# I2C_MUX.net
KiCad netlist of a schematic drawn in EAGLE
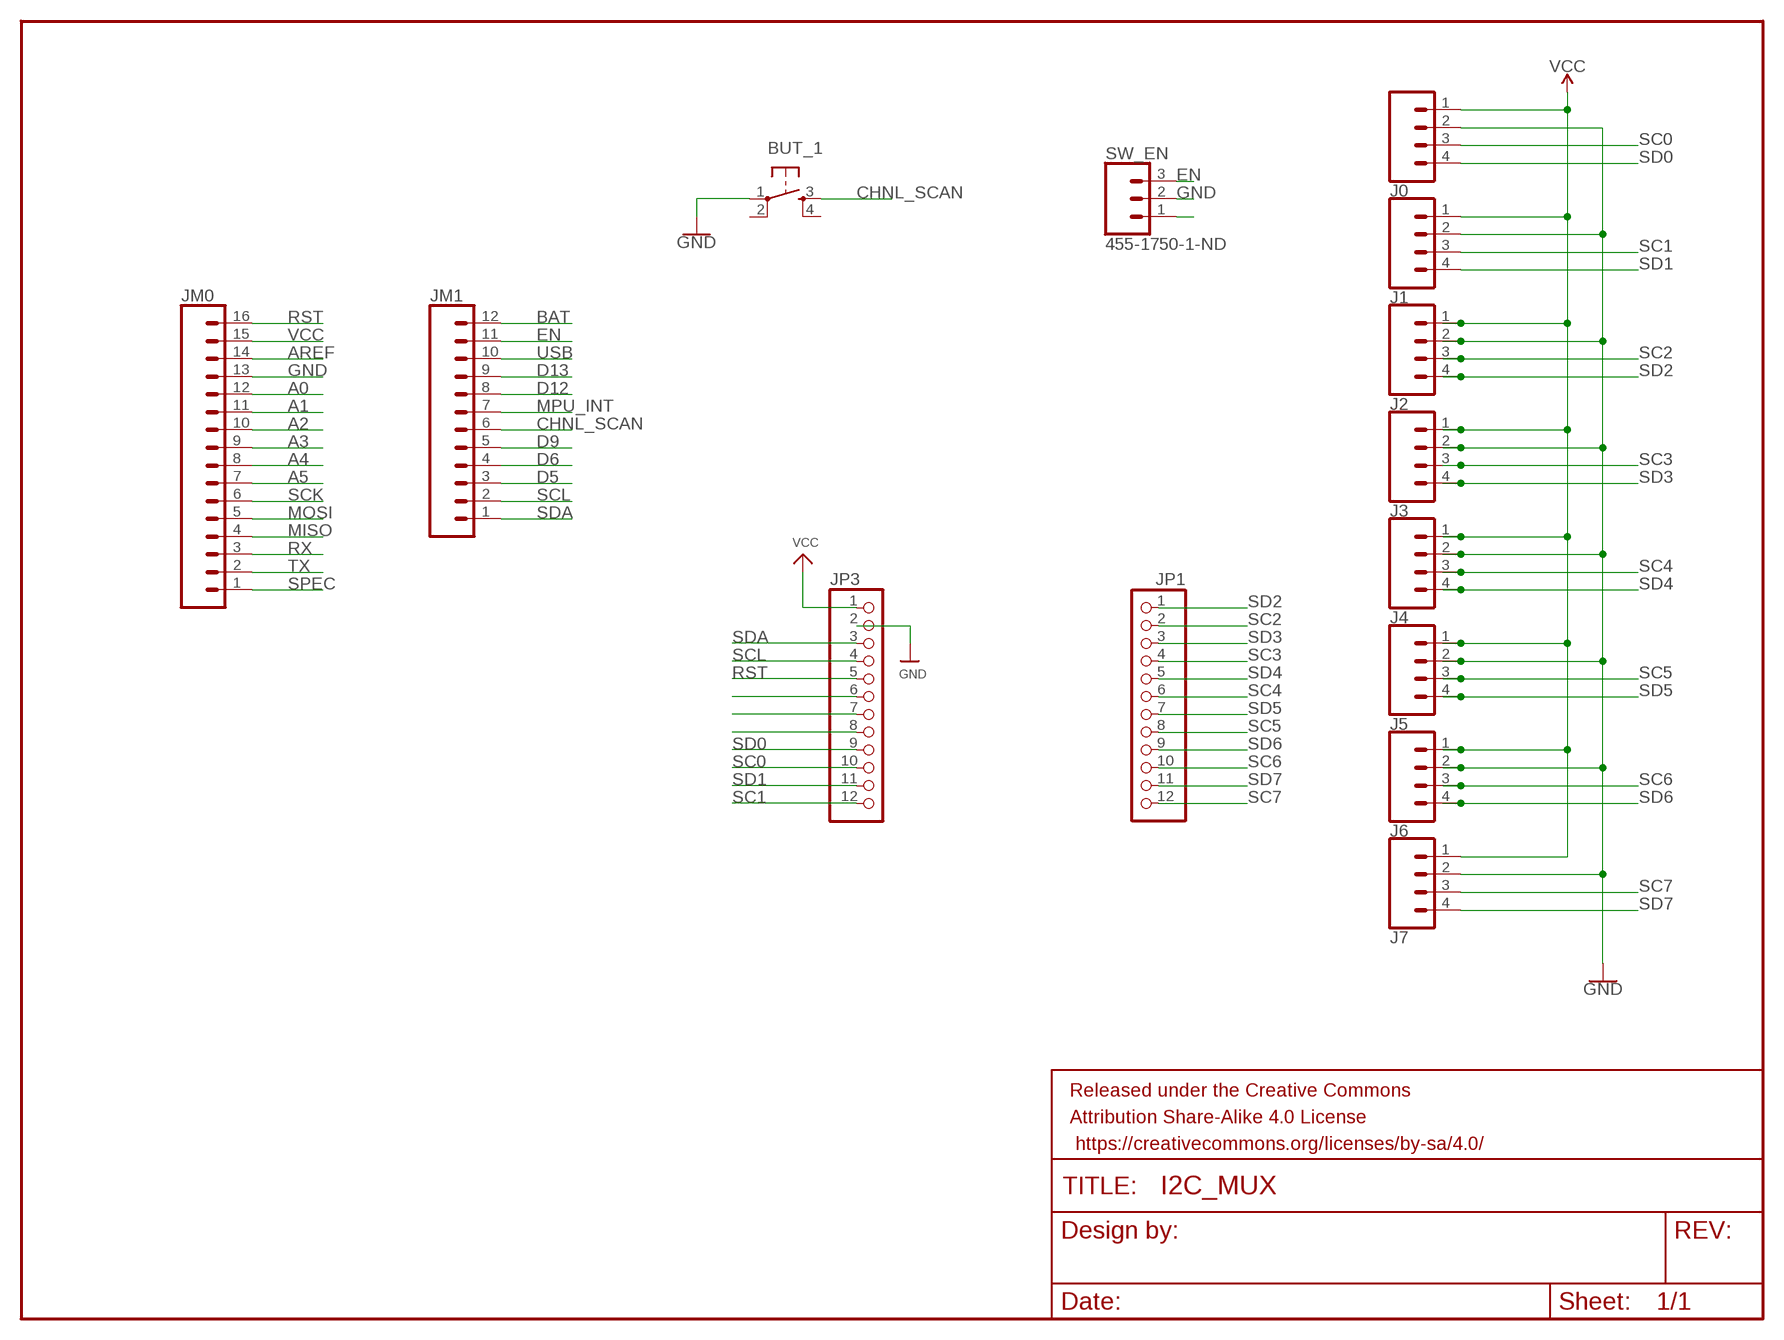
[diagram p0: schematic, sheet 1]

(export (version "E")
  (design (tool "Eeschema 10.0.6"))
  (components
    (comp (ref "BUT_1")
      (value "TAC_SWITCHPTH")
      (footprint "eagle-import:TACTILE-PTH")
      (libsource (lib "eagle-import") (part "TAC_SWITCHPTH"))
    )
    (comp (ref "FRAME1")
      (value "FRAME-LETTER")
      (footprint "eagle-import:CREATIVE_COMMONS")
      (libsource (lib "eagle-import") (part "FRAME-LETTER"))
    )
    (comp (ref "J0")
      (value "CONN_04POLAR")
      (footprint "eagle-import:MOLEX-1X4")
      (libsource (lib "eagle-import") (part "CONN_04POLAR"))
    )
    (comp (ref "J1")
      (value "CONN_04POLAR")
      (footprint "eagle-import:MOLEX-1X4")
      (libsource (lib "eagle-import") (part "CONN_04POLAR"))
    )
    (comp (ref "J2")
      (value "CONN_04POLAR")
      (footprint "eagle-import:MOLEX-1X4")
      (libsource (lib "eagle-import") (part "CONN_04POLAR"))
    )
    (comp (ref "J3")
      (value "CONN_04POLAR")
      (footprint "eagle-import:MOLEX-1X4")
      (libsource (lib "eagle-import") (part "CONN_04POLAR"))
    )
    (comp (ref "J4")
      (value "CONN_04POLAR")
      (footprint "eagle-import:MOLEX-1X4")
      (libsource (lib "eagle-import") (part "CONN_04POLAR"))
    )
    (comp (ref "J5")
      (value "CONN_04POLAR")
      (footprint "eagle-import:MOLEX-1X4")
      (libsource (lib "eagle-import") (part "CONN_04POLAR"))
    )
    (comp (ref "J6")
      (value "CONN_04POLAR")
      (footprint "eagle-import:MOLEX-1X4")
      (libsource (lib "eagle-import") (part "CONN_04POLAR"))
    )
    (comp (ref "J7")
      (value "CONN_04POLAR")
      (footprint "eagle-import:MOLEX-1X4")
      (libsource (lib "eagle-import") (part "CONN_04POLAR"))
    )
    (comp (ref "JM0")
      (value "CONN_16")
      (footprint "eagle-import:1X16")
      (libsource (lib "eagle-import") (part "CONN_16"))
    )
    (comp (ref "JM1")
      (value "CONN_12")
      (footprint "eagle-import:1X12")
      (libsource (lib "eagle-import") (part "CONN_12"))
    )
    (comp (ref "JP1")
      (value "HEADER-1X12")
      (footprint "eagle-import:1X12_ROUND")
      (libsource (lib "eagle-import") (part "HEADER-1X12"))
    )
    (comp (ref "JP3")
      (value "HEADER-1X12")
      (footprint "eagle-import:1X12_ROUND")
      (libsource (lib "eagle-import") (part "HEADER-1X12"))
    )
    (comp (ref "SW_EN")
      (value "455-1750-1-ND")
      (footprint "eagle-import:1X03")
      (libsource (lib "eagle-import") (part "CONN_03"))
    )
  )
  (nets
    (net (code "1") (name "/A0") (class "Default")
      (node (ref "JM0") (pin "12") (pinfunction "12_12") (pintype "passive"))
    )
    (net (code "2") (name "/A1") (class "Default")
      (node (ref "JM0") (pin "11") (pinfunction "11_11") (pintype "passive"))
    )
    (net (code "3") (name "/A2") (class "Default")
      (node (ref "JM0") (pin "10") (pinfunction "10_10") (pintype "passive"))
    )
    (net (code "4") (name "/A3") (class "Default")
      (node (ref "JM0") (pin "9") (pinfunction "9_9") (pintype "passive"))
    )
    (net (code "5") (name "/A4") (class "Default")
      (node (ref "JM0") (pin "8") (pinfunction "8_8") (pintype "passive"))
    )
    (net (code "6") (name "/A5") (class "Default")
      (node (ref "JM0") (pin "7") (pinfunction "7_7") (pintype "passive"))
    )
    (net (code "7") (name "/AREF") (class "Default")
      (node (ref "JM0") (pin "14") (pinfunction "14_14") (pintype "passive"))
    )
    (net (code "8") (name "/BAT") (class "Default")
      (node (ref "JM1") (pin "12") (pinfunction "12_12") (pintype "passive"))
    )
    (net (code "9") (name "/CHNL_SCAN") (class "Default")
      (node (ref "BUT_1") (pin "3") (pinfunction "3_3") (pintype "passive"))
      (node (ref "JM1") (pin "6") (pinfunction "6_6") (pintype "passive"))
    )
    (net (code "10") (name "/D5") (class "Default")
      (node (ref "JM1") (pin "3") (pinfunction "3_3") (pintype "passive"))
    )
    (net (code "11") (name "/D6") (class "Default")
      (node (ref "JM1") (pin "4") (pinfunction "4_4") (pintype "passive"))
    )
    (net (code "12") (name "/D9") (class "Default")
      (node (ref "JM1") (pin "5") (pinfunction "5_5") (pintype "passive"))
    )
    (net (code "13") (name "/D12") (class "Default")
      (node (ref "JM1") (pin "8") (pinfunction "8_8") (pintype "passive"))
    )
    (net (code "14") (name "/D13") (class "Default")
      (node (ref "JM1") (pin "9") (pinfunction "9_9") (pintype "passive"))
    )
    (net (code "15") (name "/EN") (class "Default")
      (node (ref "JM1") (pin "11") (pinfunction "11_11") (pintype "passive"))
      (node (ref "SW_EN") (pin "3") (pinfunction "3_3") (pintype "passive"))
    )
    (net (code "16") (name "/MISO") (class "Default")
      (node (ref "JM0") (pin "4") (pinfunction "4_4") (pintype "passive"))
    )
    (net (code "17") (name "/MOSI") (class "Default")
      (node (ref "JM0") (pin "5") (pinfunction "5_5") (pintype "passive"))
    )
    (net (code "18") (name "/MPU_INT") (class "Default")
      (node (ref "JM1") (pin "7") (pinfunction "7_7") (pintype "passive"))
    )
    (net (code "19") (name "/RST") (class "Default")
      (node (ref "JM0") (pin "16") (pinfunction "16_16") (pintype "passive"))
      (node (ref "JP3") (pin "5") (pinfunction "5_5") (pintype "passive"))
    )
    (net (code "20") (name "/RX") (class "Default")
      (node (ref "JM0") (pin "3") (pinfunction "3_3") (pintype "passive"))
    )
    (net (code "21") (name "/SC0") (class "Default")
      (node (ref "J0") (pin "3") (pinfunction "3_3") (pintype "passive"))
      (node (ref "JP3") (pin "10") (pinfunction "10_10") (pintype "passive"))
    )
    (net (code "22") (name "/SC1") (class "Default")
      (node (ref "J1") (pin "3") (pinfunction "3_3") (pintype "passive"))
      (node (ref "JP3") (pin "12") (pinfunction "12_12") (pintype "passive"))
    )
    (net (code "23") (name "/SC2") (class "Default")
      (node (ref "J2") (pin "3") (pinfunction "3_3") (pintype "passive"))
      (node (ref "JP1") (pin "2") (pinfunction "2_2") (pintype "passive"))
    )
    (net (code "24") (name "/SC3") (class "Default")
      (node (ref "J3") (pin "3") (pinfunction "3_3") (pintype "passive"))
      (node (ref "JP1") (pin "4") (pinfunction "4_4") (pintype "passive"))
    )
    (net (code "25") (name "/SC4") (class "Default")
      (node (ref "J4") (pin "3") (pinfunction "3_3") (pintype "passive"))
      (node (ref "JP1") (pin "6") (pinfunction "6_6") (pintype "passive"))
    )
    (net (code "26") (name "/SC5") (class "Default")
      (node (ref "J5") (pin "3") (pinfunction "3_3") (pintype "passive"))
      (node (ref "JP1") (pin "8") (pinfunction "8_8") (pintype "passive"))
    )
    (net (code "27") (name "/SC6") (class "Default")
      (node (ref "J6") (pin "3") (pinfunction "3_3") (pintype "passive"))
      (node (ref "JP1") (pin "10") (pinfunction "10_10") (pintype "passive"))
    )
    (net (code "28") (name "/SC7") (class "Default")
      (node (ref "J7") (pin "3") (pinfunction "3_3") (pintype "passive"))
      (node (ref "JP1") (pin "12") (pinfunction "12_12") (pintype "passive"))
    )
    (net (code "29") (name "/SCK") (class "Default")
      (node (ref "JM0") (pin "6") (pinfunction "6_6") (pintype "passive"))
    )
    (net (code "30") (name "/SCL") (class "Default")
      (node (ref "JM1") (pin "2") (pinfunction "2_2") (pintype "passive"))
      (node (ref "JP3") (pin "4") (pinfunction "4_4") (pintype "passive"))
    )
    (net (code "31") (name "/SD0") (class "Default")
      (node (ref "J0") (pin "4") (pinfunction "4_4") (pintype "passive"))
      (node (ref "JP3") (pin "9") (pinfunction "9_9") (pintype "passive"))
    )
    (net (code "32") (name "/SD1") (class "Default")
      (node (ref "J1") (pin "4") (pinfunction "4_4") (pintype "passive"))
      (node (ref "JP3") (pin "11") (pinfunction "11_11") (pintype "passive"))
    )
    (net (code "33") (name "/SD2") (class "Default")
      (node (ref "J2") (pin "4") (pinfunction "4_4") (pintype "passive"))
      (node (ref "JP1") (pin "1") (pinfunction "1_1") (pintype "passive"))
    )
    (net (code "34") (name "/SD3") (class "Default")
      (node (ref "J3") (pin "4") (pinfunction "4_4") (pintype "passive"))
      (node (ref "JP1") (pin "3") (pinfunction "3_3") (pintype "passive"))
    )
    (net (code "35") (name "/SD4") (class "Default")
      (node (ref "J4") (pin "4") (pinfunction "4_4") (pintype "passive"))
      (node (ref "JP1") (pin "5") (pinfunction "5_5") (pintype "passive"))
    )
    (net (code "36") (name "/SD5") (class "Default")
      (node (ref "J5") (pin "4") (pinfunction "4_4") (pintype "passive"))
      (node (ref "JP1") (pin "7") (pinfunction "7_7") (pintype "passive"))
    )
    (net (code "37") (name "/SD6") (class "Default")
      (node (ref "J6") (pin "4") (pinfunction "4_4") (pintype "passive"))
      (node (ref "JP1") (pin "9") (pinfunction "9_9") (pintype "passive"))
    )
    (net (code "38") (name "/SD7") (class "Default")
      (node (ref "J7") (pin "4") (pinfunction "4_4") (pintype "passive"))
      (node (ref "JP1") (pin "11") (pinfunction "11_11") (pintype "passive"))
    )
    (net (code "39") (name "/SDA") (class "Default")
      (node (ref "JM1") (pin "1") (pinfunction "1_1") (pintype "passive"))
      (node (ref "JP3") (pin "3") (pinfunction "3_3") (pintype "passive"))
    )
    (net (code "40") (name "/SPEC") (class "Default")
      (node (ref "JM0") (pin "1") (pinfunction "1_1") (pintype "passive"))
    )
    (net (code "41") (name "/TX") (class "Default")
      (node (ref "JM0") (pin "2") (pinfunction "2_2") (pintype "passive"))
    )
    (net (code "42") (name "/USB") (class "Default")
      (node (ref "JM1") (pin "10") (pinfunction "10_10") (pintype "passive"))
    )
    (net (code "43") (name "GND") (class "Default")
      (node (ref "BUT_1") (pin "1") (pinfunction "1_1") (pintype "passive"))
      (node (ref "J0") (pin "2") (pinfunction "2_2") (pintype "passive"))
      (node (ref "J1") (pin "2") (pinfunction "2_2") (pintype "passive"))
      (node (ref "J2") (pin "2") (pinfunction "2_2") (pintype "passive"))
      (node (ref "J3") (pin "2") (pinfunction "2_2") (pintype "passive"))
      (node (ref "J4") (pin "2") (pinfunction "2_2") (pintype "passive"))
      (node (ref "J5") (pin "2") (pinfunction "2_2") (pintype "passive"))
      (node (ref "J6") (pin "2") (pinfunction "2_2") (pintype "passive"))
      (node (ref "J7") (pin "2") (pinfunction "2_2") (pintype "passive"))
      (node (ref "JM0") (pin "13") (pinfunction "13_13") (pintype "passive"))
      (node (ref "JP3") (pin "2") (pinfunction "2_2") (pintype "passive"))
      (node (ref "SW_EN") (pin "2") (pinfunction "2_2") (pintype "passive"))
    )
    (net (code "44") (name "VCC") (class "Default")
      (node (ref "J0") (pin "1") (pinfunction "1_1") (pintype "passive"))
      (node (ref "J1") (pin "1") (pinfunction "1_1") (pintype "passive"))
      (node (ref "J2") (pin "1") (pinfunction "1_1") (pintype "passive"))
      (node (ref "J3") (pin "1") (pinfunction "1_1") (pintype "passive"))
      (node (ref "J4") (pin "1") (pinfunction "1_1") (pintype "passive"))
      (node (ref "J5") (pin "1") (pinfunction "1_1") (pintype "passive"))
      (node (ref "J6") (pin "1") (pinfunction "1_1") (pintype "passive"))
      (node (ref "J7") (pin "1") (pinfunction "1_1") (pintype "passive"))
      (node (ref "JM0") (pin "15") (pinfunction "15_15") (pintype "passive"))
      (node (ref "JP3") (pin "1") (pinfunction "1_1") (pintype "passive"))
    )
    (net (code "45") (name "unconnected-(BUT_1-Pad2)") (class "Default")
      (node (ref "BUT_1") (pin "2") (pinfunction "2_2") (pintype "passive"))
    )
    (net (code "46") (name "unconnected-(BUT_1-Pad4)") (class "Default")
      (node (ref "BUT_1") (pin "4") (pinfunction "4_4") (pintype "passive"))
    )
    (net (code "47") (name "unconnected-(JP3-Pad6)") (class "Default")
      (node (ref "JP3") (pin "6") (pinfunction "6_6") (pintype "passive"))
    )
    (net (code "48") (name "unconnected-(JP3-Pad7)") (class "Default")
      (node (ref "JP3") (pin "7") (pinfunction "7_7") (pintype "passive"))
    )
    (net (code "49") (name "unconnected-(JP3-Pad8)") (class "Default")
      (node (ref "JP3") (pin "8") (pinfunction "8_8") (pintype "passive"))
    )
    (net (code "50") (name "unconnected-(SW_EN-Pad1)") (class "Default")
      (node (ref "SW_EN") (pin "1") (pinfunction "1_1") (pintype "passive"))
    )
  )
)
